# rimocon.net
KiCad netlist of a schematic drawn in EAGLE
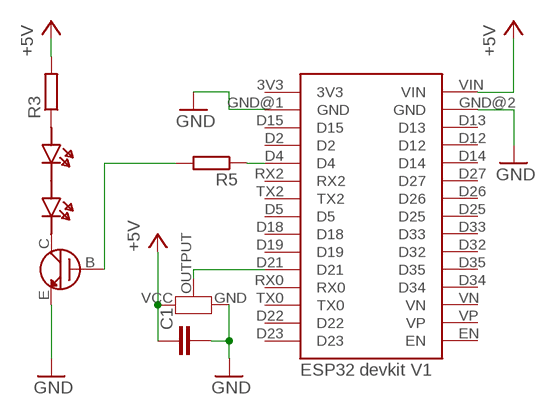
[diagram p0: schematic, sheet 1]

(export (version "E")
  (design (tool "Eeschema 10.0.6"))
  (components
    (comp (ref "C1")
      (value "C-EU025-024X044")
      (footprint "eagle-import:C025-024X044")
      (libsource (lib "eagle-import") (part "C-EU025-024X044"))
    )
    (comp (ref "R3")
      (value "R-EU_0204/5")
      (footprint "eagle-import:0204_5")
      (libsource (lib "eagle-import") (part "R-EU_0204/5"))
    )
    (comp (ref "R5")
      (value "R-EU_0204/5")
      (footprint "eagle-import:0204_5")
      (libsource (lib "eagle-import") (part "R-EU_0204/5"))
    )
    (comp (ref "U$1")
      (value "2SC1815")
      (footprint "eagle-import:1815")
      (libsource (lib "eagle-import") (part "2SC1815"))
    )
    (comp (ref "U$2")
      (value "OSRB38C9AA")
      (footprint "eagle-import:OSRB38")
      (libsource (lib "eagle-import") (part "OSRB38C9AA"))
    )
    (comp (ref "U$3")
      (value "ESP32DEVKITV1")
      (footprint "eagle-import:ESP32DEVKITV1")
      (libsource (lib "eagle-import") (part "ESP32DEVKITV1"))
    )
    (comp (ref "U$5")
      (value "LEDOSI5FU3A11C")
      (footprint "eagle-import:OSI5FU3A11C")
      (libsource (lib "eagle-import") (part "LEDOSI5FU3A11C"))
    )
    (comp (ref "U$6")
      (value "LEDOSI5FU3A11C")
      (footprint "eagle-import:OSI5FU3A11C")
      (libsource (lib "eagle-import") (part "LEDOSI5FU3A11C"))
    )
  )
  (nets
    (net (code "1") (name "+5V") (class "Default")
      (node (ref "C1") (pin "1") (pinfunction "1_1") (pintype "passive"))
      (node (ref "R3") (pin "2") (pinfunction "2_2") (pintype "passive"))
      (node (ref "U$2") (pin "VCC") (pinfunction "VCC_VCC") (pintype "power_in"))
      (node (ref "U$3") (pin "VIN") (pinfunction "VIN_VIN") (pintype "power_in"))
    )
    (net (code "2") (name "/3V3") (class "Default")
      (node (ref "U$3") (pin "3V3") (pinfunction "3V3_3V3") (pintype "power_in"))
    )
    (net (code "3") (name "GND") (class "Default")
      (node (ref "C1") (pin "2") (pinfunction "2_2") (pintype "passive"))
      (node (ref "U$1") (pin "E") (pinfunction "E_E") (pintype "bidirectional"))
      (node (ref "U$2") (pin "GND") (pinfunction "GND_GND") (pintype "power_in"))
      (node (ref "U$3") (pin "GND@1") (pinfunction "GND_GND@1") (pintype "power_in"))
      (node (ref "U$3") (pin "GND@2") (pinfunction "GND_GND@2") (pintype "power_in"))
    )
    (net (code "4") (name "Net-(R5-Pad1)") (class "Default")
      (node (ref "R5") (pin "1") (pinfunction "1_1") (pintype "passive"))
      (node (ref "U$3") (pin "D4") (pinfunction "D4_D4") (pintype "bidirectional"))
    )
    (net (code "5") (name "Net-(R5-Pad2)") (class "Default")
      (node (ref "R5") (pin "2") (pinfunction "2_2") (pintype "passive"))
      (node (ref "U$1") (pin "B") (pinfunction "B_B") (pintype "bidirectional"))
    )
    (net (code "6") (name "Net-(U$2-PadOUTPUT)") (class "Default")
      (node (ref "U$2") (pin "OUTPUT") (pinfunction "OUTPUT_OUTPUT") (pintype "bidirectional"))
      (node (ref "U$3") (pin "D21") (pinfunction "D21_D21") (pintype "bidirectional"))
    )
    (net (code "7") (name "Net-(U$5-ANODE)") (class "Default")
      (node (ref "U$5") (pin "A") (pinfunction "ANODE_A") (pintype "bidirectional"))
      (node (ref "U$6") (pin "K") (pinfunction "CATHODE_K") (pintype "bidirectional"))
    )
    (net (code "8") (name "Net-(U$5-CATHODE)") (class "Default")
      (node (ref "U$1") (pin "C") (pinfunction "C_C") (pintype "bidirectional"))
      (node (ref "U$5") (pin "K") (pinfunction "CATHODE_K") (pintype "bidirectional"))
    )
    (net (code "9") (name "Net-(U$6-ANODE)") (class "Default")
      (node (ref "R3") (pin "1") (pinfunction "1_1") (pintype "passive"))
      (node (ref "U$6") (pin "A") (pinfunction "ANODE_A") (pintype "bidirectional"))
    )
    (net (code "10") (name "unconnected-(U$3-PadD2)") (class "Default")
      (node (ref "U$3") (pin "D2") (pinfunction "D2_D2") (pintype "bidirectional"))
    )
    (net (code "11") (name "unconnected-(U$3-PadD5)") (class "Default")
      (node (ref "U$3") (pin "D5") (pinfunction "D5_D5") (pintype "bidirectional"))
    )
    (net (code "12") (name "unconnected-(U$3-PadD12)") (class "Default")
      (node (ref "U$3") (pin "D12") (pinfunction "D12_D12") (pintype "bidirectional"))
    )
    (net (code "13") (name "unconnected-(U$3-PadD13)") (class "Default")
      (node (ref "U$3") (pin "D13") (pinfunction "D13_D13") (pintype "bidirectional"))
    )
    (net (code "14") (name "unconnected-(U$3-PadD14)") (class "Default")
      (node (ref "U$3") (pin "D14") (pinfunction "D14_D14") (pintype "bidirectional"))
    )
    (net (code "15") (name "unconnected-(U$3-PadD15)") (class "Default")
      (node (ref "U$3") (pin "D15") (pinfunction "D15_D15") (pintype "bidirectional"))
    )
    (net (code "16") (name "unconnected-(U$3-PadD18)") (class "Default")
      (node (ref "U$3") (pin "D18") (pinfunction "D18_D18") (pintype "bidirectional"))
    )
    (net (code "17") (name "unconnected-(U$3-PadD19)") (class "Default")
      (node (ref "U$3") (pin "D19") (pinfunction "D19_D19") (pintype "bidirectional"))
    )
    (net (code "18") (name "unconnected-(U$3-PadD22)") (class "Default")
      (node (ref "U$3") (pin "D22") (pinfunction "D22_D22") (pintype "bidirectional"))
    )
    (net (code "19") (name "unconnected-(U$3-PadD23)") (class "Default")
      (node (ref "U$3") (pin "D23") (pinfunction "D23_D23") (pintype "bidirectional"))
    )
    (net (code "20") (name "unconnected-(U$3-PadD25)") (class "Default")
      (node (ref "U$3") (pin "D25") (pinfunction "D25_D25") (pintype "bidirectional"))
    )
    (net (code "21") (name "unconnected-(U$3-PadD26)") (class "Default")
      (node (ref "U$3") (pin "D26") (pinfunction "D26_D26") (pintype "bidirectional"))
    )
    (net (code "22") (name "unconnected-(U$3-PadD27)") (class "Default")
      (node (ref "U$3") (pin "D27") (pinfunction "D27_D27") (pintype "bidirectional"))
    )
    (net (code "23") (name "unconnected-(U$3-PadD32)") (class "Default")
      (node (ref "U$3") (pin "D32") (pinfunction "D32_D32") (pintype "bidirectional"))
    )
    (net (code "24") (name "unconnected-(U$3-PadD33)") (class "Default")
      (node (ref "U$3") (pin "D33") (pinfunction "D33_D33") (pintype "bidirectional"))
    )
    (net (code "25") (name "unconnected-(U$3-PadD34)") (class "Default")
      (node (ref "U$3") (pin "D34") (pinfunction "D34_D34") (pintype "bidirectional"))
    )
    (net (code "26") (name "unconnected-(U$3-PadD35)") (class "Default")
      (node (ref "U$3") (pin "D35") (pinfunction "D35_D35") (pintype "bidirectional"))
    )
    (net (code "27") (name "unconnected-(U$3-PadEN)") (class "Default")
      (node (ref "U$3") (pin "EN") (pinfunction "EN_EN") (pintype "bidirectional"))
    )
    (net (code "28") (name "unconnected-(U$3-PadRX0)") (class "Default")
      (node (ref "U$3") (pin "RX0") (pinfunction "RX0_RX0") (pintype "bidirectional"))
    )
    (net (code "29") (name "unconnected-(U$3-PadRX2)") (class "Default")
      (node (ref "U$3") (pin "RX2") (pinfunction "RX2_RX2") (pintype "bidirectional"))
    )
    (net (code "30") (name "unconnected-(U$3-PadTX0)") (class "Default")
      (node (ref "U$3") (pin "TX0") (pinfunction "TX0_TX0") (pintype "bidirectional"))
    )
    (net (code "31") (name "unconnected-(U$3-PadTX2)") (class "Default")
      (node (ref "U$3") (pin "TX2") (pinfunction "TX2_TX2") (pintype "bidirectional"))
    )
    (net (code "32") (name "unconnected-(U$3-PadVN)") (class "Default")
      (node (ref "U$3") (pin "VN") (pinfunction "VN_VN") (pintype "bidirectional"))
    )
    (net (code "33") (name "unconnected-(U$3-PadVP)") (class "Default")
      (node (ref "U$3") (pin "VP") (pinfunction "VP_VP") (pintype "bidirectional"))
    )
  )
)
